# imu_node.net
KiCad netlist of a schematic drawn in EAGLE
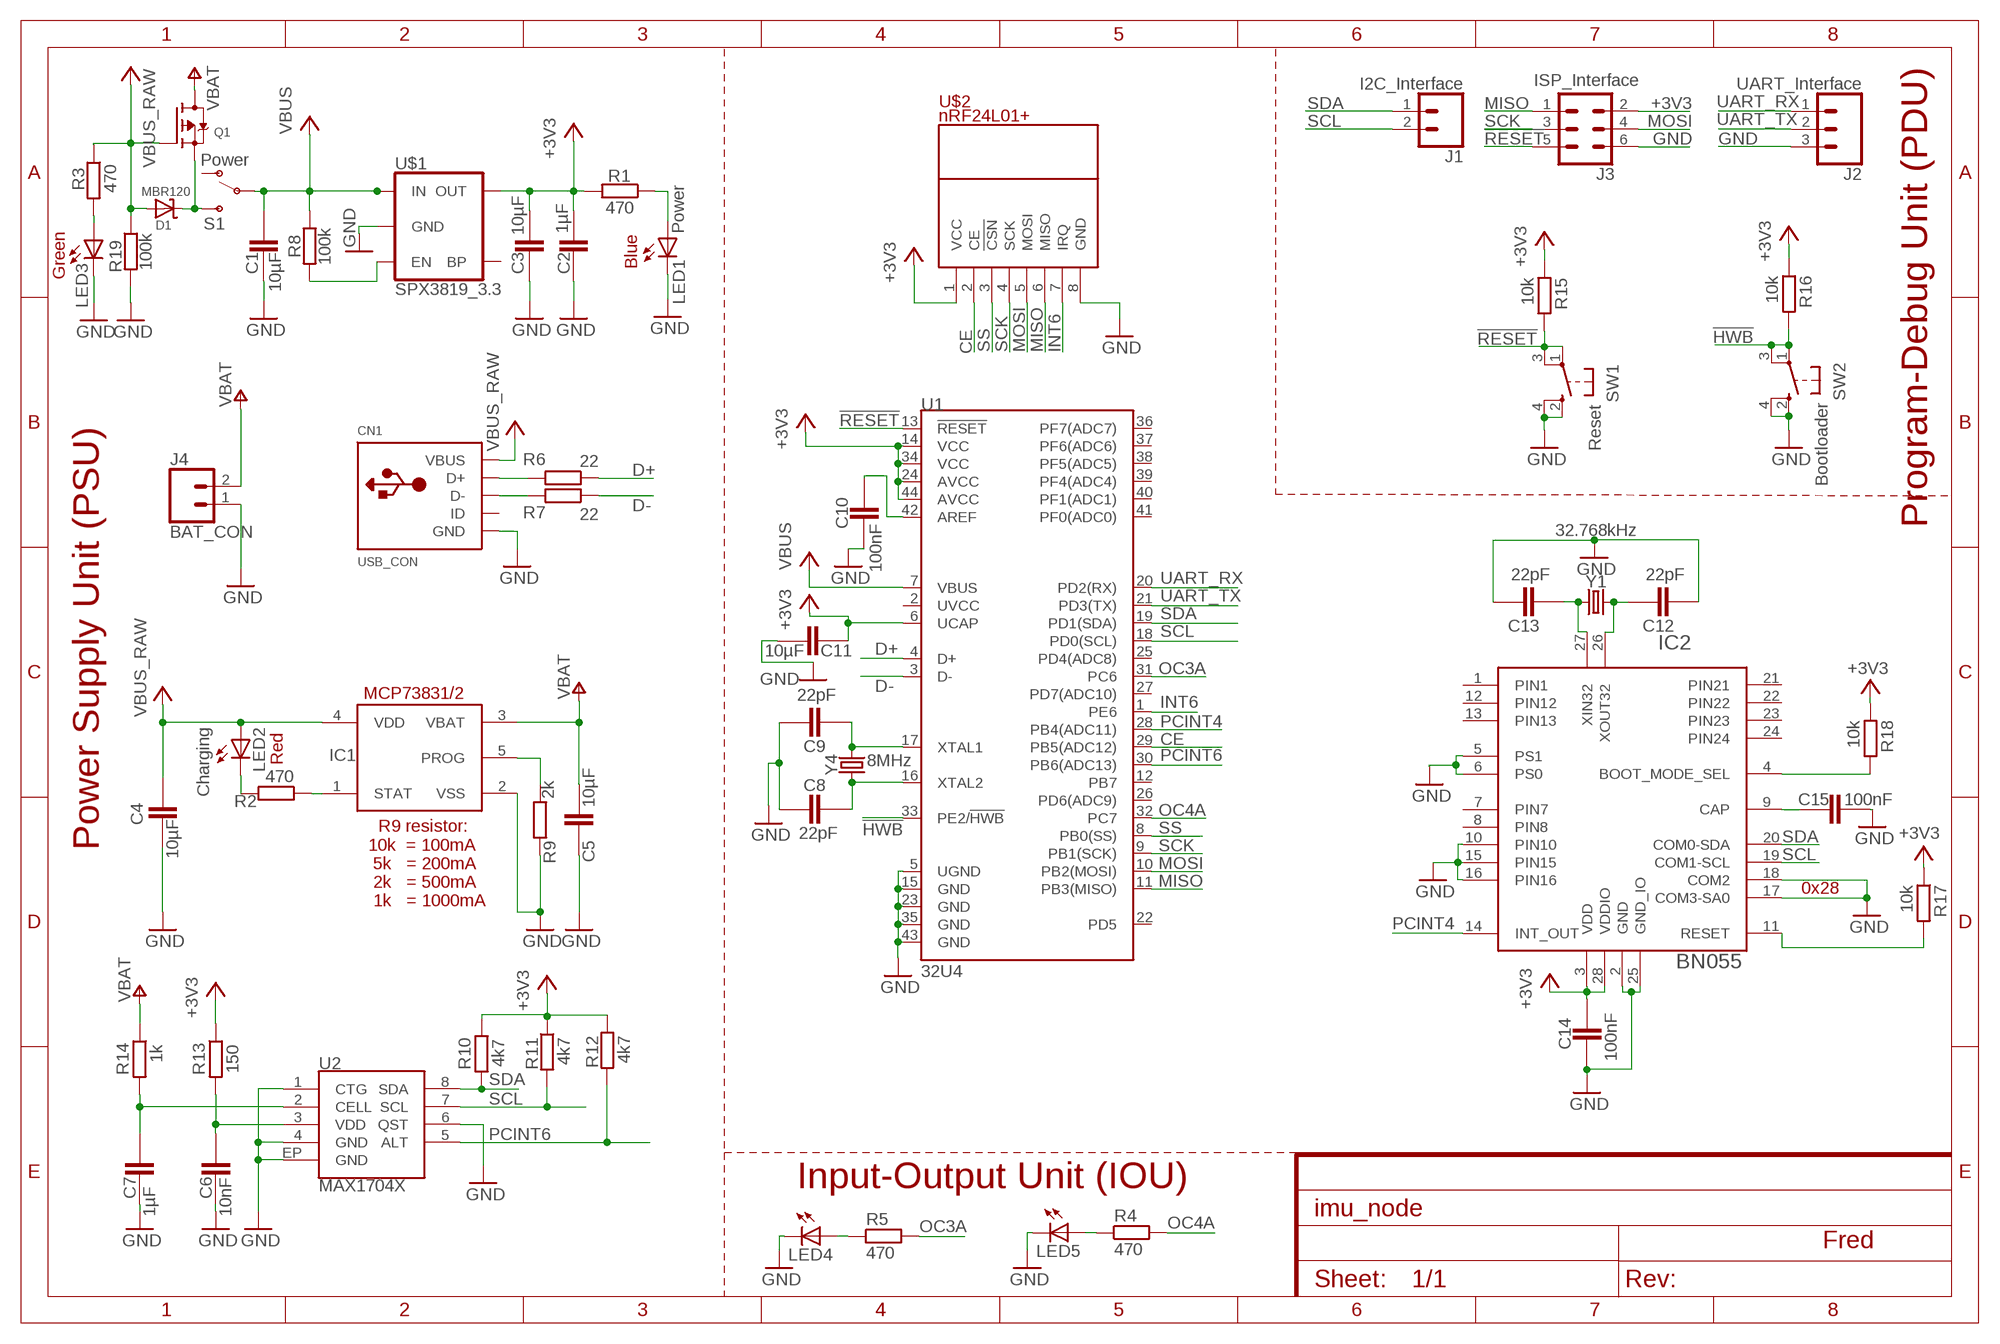
[diagram p0: schematic, sheet 1]

(export (version "E")
  (design (tool "Eeschema 10.0.6"))
  (components
    (comp (ref "C1")
      (value "10µF")
      (footprint "eagle-import:CAPC1608X92N")
      (libsource (lib "eagle-import") (part "CAPACITOR_0603"))
    )
    (comp (ref "C2")
      (value "1µF")
      (footprint "eagle-import:CAPC1608X92N")
      (libsource (lib "eagle-import") (part "CAPACITOR_0603"))
    )
    (comp (ref "C3")
      (value "10µF")
      (footprint "eagle-import:CAPC1608X92N")
      (libsource (lib "eagle-import") (part "CAPACITOR_0603"))
    )
    (comp (ref "C4")
      (value "10µF")
      (footprint "eagle-import:CAPC1608X92N")
      (libsource (lib "eagle-import") (part "CAPACITOR_0603"))
    )
    (comp (ref "C5")
      (value "10µF")
      (footprint "eagle-import:CAPC1608X92N")
      (libsource (lib "eagle-import") (part "CAPACITOR_0603"))
    )
    (comp (ref "C6")
      (value "10nF")
      (footprint "eagle-import:CAPC1608X92N")
      (libsource (lib "eagle-import") (part "CAPACITOR_0603"))
    )
    (comp (ref "C7")
      (value "1µF")
      (footprint "eagle-import:CAPC1608X92N")
      (libsource (lib "eagle-import") (part "CAPACITOR_0603"))
    )
    (comp (ref "C8")
      (value "22pF")
      (footprint "eagle-import:CAPC1608X92N")
      (libsource (lib "eagle-import") (part "CAPACITOR_0603"))
    )
    (comp (ref "C9")
      (value "22pF")
      (footprint "eagle-import:CAPC1608X92N")
      (libsource (lib "eagle-import") (part "CAPACITOR_0603"))
    )
    (comp (ref "C10")
      (value "100nF")
      (footprint "eagle-import:CAPC1608X92N")
      (libsource (lib "eagle-import") (part "CAPACITOR_0603"))
    )
    (comp (ref "C11")
      (value "10µF")
      (footprint "eagle-import:CAPC1608X92N")
      (libsource (lib "eagle-import") (part "CAPACITOR_0603"))
    )
    (comp (ref "C12")
      (value "22pF")
      (footprint "eagle-import:CAPC1608X92N")
      (libsource (lib "eagle-import") (part "CAPACITOR_0603"))
    )
    (comp (ref "C13")
      (value "22pF")
      (footprint "eagle-import:CAPC1608X92N")
      (libsource (lib "eagle-import") (part "CAPACITOR_0603"))
    )
    (comp (ref "C14")
      (value "100nF")
      (footprint "eagle-import:CAPC1608X92N")
      (libsource (lib "eagle-import") (part "CAPACITOR_0603"))
    )
    (comp (ref "C15")
      (value "100nF")
      (footprint "eagle-import:CAPC1608X92N")
      (libsource (lib "eagle-import") (part "CAPACITOR_0603"))
    )
    (comp (ref "CN1")
      (value "USB_CON")
      (footprint "eagle-import:USB-MINIB")
      (libsource (lib "eagle-import") (part "USBMINIB"))
    )
    (comp (ref "D1")
      (value "MBR120")
      (footprint "eagle-import:SOD-123FL")
      (libsource (lib "eagle-import") (part "DIODE_SOD-123FL"))
    )
    (comp (ref "IC1")
      (value "MCP73831/OT")
      (footprint "eagle-import:SOT23-5L")
      (libsource (lib "eagle-import") (part "MCP73831/OT"))
    )
    (comp (ref "IC2")
      (value "BN055")
      (footprint "eagle-import:LGA-28_3.80X5.20_0.5")
      (fields (field (name "PART_NUMBER") "BNO055"))
      (libsource (lib "eagle-import") (part "1658_BNO055"))
    )
    (comp (ref "J1")
      (value "I2C_Interface")
      (footprint "eagle-import:1X02")
      (libsource (lib "eagle-import") (part "CONN_02"))
    )
    (comp (ref "J2")
      (value "UART_Interface")
      (footprint "eagle-import:1X03")
      (libsource (lib "eagle-import") (part "CONN_03"))
    )
    (comp (ref "J3")
      (value "ISP_Interface")
      (footprint "eagle-import:2X3")
      (libsource (lib "eagle-import") (part "CONN_03X2FEMALE"))
    )
    (comp (ref "J4")
      (value "BAT_CON")
      (footprint "eagle-import:1X02")
      (libsource (lib "eagle-import") (part "CONN_02"))
    )
    (comp (ref "LED1")
      (value "Power")
      (footprint "eagle-import:CHIPLED_0603")
      (libsource (lib "eagle-import") (part "LEDCHIPLED_0603"))
    )
    (comp (ref "LED2")
      (value "Charging")
      (footprint "eagle-import:CHIPLED_0603")
      (libsource (lib "eagle-import") (part "LEDCHIPLED_0603"))
    )
    (comp (ref "LED3")
      (value "USB")
      (footprint "eagle-import:CHIPLED_0603")
      (libsource (lib "eagle-import") (part "LEDCHIPLED_0603"))
    )
    (comp (ref "LED4")
      (value "LEDCHIPLED_0603")
      (footprint "eagle-import:CHIPLED_0603")
      (libsource (lib "eagle-import") (part "LEDCHIPLED_0603"))
    )
    (comp (ref "LED5")
      (value "LEDCHIPLED_0603")
      (footprint "eagle-import:CHIPLED_0603")
      (libsource (lib "eagle-import") (part "LEDCHIPLED_0603"))
    )
    (comp (ref "Q1")
      (value "MICROBUILDER_MOSFET-P")
      (footprint "eagle-import:MICROBUILDER_SOT23-R")
      (libsource (lib "eagle-import") (part "MICROBUILDER_MOSFET-P"))
    )
    (comp (ref "R1")
      (value "470")
      (footprint "eagle-import:RESC1608X55N")
      (libsource (lib "eagle-import") (part "RESISTOR_0603"))
    )
    (comp (ref "R2")
      (value "470")
      (footprint "eagle-import:RESC1608X55N")
      (libsource (lib "eagle-import") (part "RESISTOR_0603"))
    )
    (comp (ref "R3")
      (value "470")
      (footprint "eagle-import:RESC1608X55N")
      (libsource (lib "eagle-import") (part "RESISTOR_0603"))
    )
    (comp (ref "R4")
      (value "470")
      (footprint "eagle-import:RESC1608X55N")
      (libsource (lib "eagle-import") (part "RESISTOR_0603"))
    )
    (comp (ref "R5")
      (value "470")
      (footprint "eagle-import:RESC1608X55N")
      (libsource (lib "eagle-import") (part "RESISTOR_0603"))
    )
    (comp (ref "R6")
      (value "22")
      (footprint "eagle-import:RESC1608X55N")
      (libsource (lib "eagle-import") (part "RESISTOR_0603"))
    )
    (comp (ref "R7")
      (value "22")
      (footprint "eagle-import:RESC1608X55N")
      (libsource (lib "eagle-import") (part "RESISTOR_0603"))
    )
    (comp (ref "R8")
      (value "100k")
      (footprint "eagle-import:RESC1608X55N")
      (libsource (lib "eagle-import") (part "RESISTOR_0603"))
    )
    (comp (ref "R9")
      (value "2k")
      (footprint "eagle-import:RESC1608X55N")
      (libsource (lib "eagle-import") (part "RESISTOR_0603"))
    )
    (comp (ref "R10")
      (value "4k7")
      (footprint "eagle-import:RESC1608X55N")
      (libsource (lib "eagle-import") (part "RESISTOR_0603"))
    )
    (comp (ref "R11")
      (value "4k7")
      (footprint "eagle-import:RESC1608X55N")
      (libsource (lib "eagle-import") (part "RESISTOR_0603"))
    )
    (comp (ref "R12")
      (value "4k7")
      (footprint "eagle-import:RESC1608X55N")
      (libsource (lib "eagle-import") (part "RESISTOR_0603"))
    )
    (comp (ref "R13")
      (value "150")
      (footprint "eagle-import:RESC1608X55N")
      (libsource (lib "eagle-import") (part "RESISTOR_0603"))
    )
    (comp (ref "R14")
      (value "1k")
      (footprint "eagle-import:RESC1608X55N")
      (libsource (lib "eagle-import") (part "RESISTOR_0603"))
    )
    (comp (ref "R15")
      (value "10k")
      (footprint "eagle-import:RESC1608X55N")
      (libsource (lib "eagle-import") (part "RESISTOR_0603"))
    )
    (comp (ref "R16")
      (value "10k")
      (footprint "eagle-import:RESC1608X55N")
      (libsource (lib "eagle-import") (part "RESISTOR_0603"))
    )
    (comp (ref "R17")
      (value "10k")
      (footprint "eagle-import:RESC1608X55N")
      (libsource (lib "eagle-import") (part "RESISTOR_0603"))
    )
    (comp (ref "R18")
      (value "10k")
      (footprint "eagle-import:RESC1608X55N")
      (libsource (lib "eagle-import") (part "RESISTOR_0603"))
    )
    (comp (ref "R19")
      (value "100k")
      (footprint "eagle-import:RESC1608X55N")
      (libsource (lib "eagle-import") (part "RESISTOR_0603"))
    )
    (comp (ref "S1")
      (value "Power")
      (footprint "eagle-import:SWITCH_SPST_SMD_A")
      (libsource (lib "eagle-import") (part "SWITCH-SPDT-SMD-RIGHT-ANGLE"))
    )
    (comp (ref "SW1")
      (value "Reset")
      (footprint "eagle-import:KMR2")
      (libsource (lib "eagle-import") (part "SPST_TACT-KMR2"))
    )
    (comp (ref "SW2")
      (value "Bootloader")
      (footprint "eagle-import:KMR2")
      (libsource (lib "eagle-import") (part "SPST_TACT-KMR2"))
    )
    (comp (ref "U$1")
      (value "SPX3819_3.3")
      (footprint "eagle-import:SOT23-5")
      (libsource (lib "eagle-import") (part "V_REG_SPX3819-SOT23-5"))
    )
    (comp (ref "U$2")
      (value "nRF24L01+")
      (footprint "eagle-import:6-PIN-BREAKOUT")
      (libsource (lib "eagle-import") (part "6-PIN-BREAKOUT6-PIN-BREAKOUT"))
    )
    (comp (ref "U1")
      (value "32U4")
      (footprint "eagle-import:TQFP44")
      (libsource (lib "eagle-import") (part "ATMEGA32U4TQFP-44"))
    )
    (comp (ref "U2")
      (value "MAX1704X")
      (footprint "eagle-import:TDFN-8")
      (libsource (lib "eagle-import") (part "MAX1704X"))
    )
    (comp (ref "Y1")
      (value "32.768kHz")
      (footprint "eagle-import:CRYSTAL-SMD-3.2X1.5MM")
      (libsource (lib "eagle-import") (part "CRYSTAL-32.768KHZSMD-3.2X1.5"))
    )
    (comp (ref "Y4")
      (value "8MHz")
      (footprint "eagle-import:CRYSTAL-SMD-5X3.2-4PAD")
      (libsource (lib "eagle-import") (part "CRYSTAL-8MHZSMD-5X3.2"))
    )
  )
  (nets
    (net (code "1") (name "+3V3") (class "Default")
      (node (ref "C11") (pin "1") (pinfunction "1_1") (pintype "passive"))
      (node (ref "C14") (pin "1") (pinfunction "1_1") (pintype "passive"))
      (node (ref "C2") (pin "2") (pinfunction "2_2") (pintype "passive"))
      (node (ref "C3") (pin "2") (pinfunction "2_2") (pintype "passive"))
      (node (ref "IC2") (pin "28") (pinfunction "VDDIO_28") (pintype "power_in"))
      (node (ref "IC2") (pin "3") (pinfunction "VDD_3") (pintype "power_in"))
      (node (ref "J3") (pin "2") (pinfunction "2_2") (pintype "bidirectional"))
      (node (ref "R1") (pin "2") (pinfunction "2_2") (pintype "passive"))
      (node (ref "R10") (pin "1") (pinfunction "1_1") (pintype "passive"))
      (node (ref "R11") (pin "1") (pinfunction "1_1") (pintype "passive"))
      (node (ref "R12") (pin "1") (pinfunction "1_1") (pintype "passive"))
      (node (ref "R13") (pin "1") (pinfunction "1_1") (pintype "passive"))
      (node (ref "R15") (pin "1") (pinfunction "1_1") (pintype "passive"))
      (node (ref "R16") (pin "1") (pinfunction "1_1") (pintype "passive"))
      (node (ref "R17") (pin "1") (pinfunction "1_1") (pintype "passive"))
      (node (ref "R18") (pin "1") (pinfunction "1_1") (pintype "passive"))
      (node (ref "U$1") (pin "5") (pinfunction "OUT_5") (pintype "passive"))
      (node (ref "U$2") (pin "1") (pinfunction "VCC_1") (pintype "bidirectional"))
      (node (ref "U1") (pin "14") (pinfunction "VCC_14") (pintype "bidirectional"))
      (node (ref "U1") (pin "24") (pinfunction "AVCC_24") (pintype "bidirectional"))
      (node (ref "U1") (pin "34") (pinfunction "VCC_34") (pintype "bidirectional"))
      (node (ref "U1") (pin "44") (pinfunction "AVCC_44") (pintype "bidirectional"))
      (node (ref "U1") (pin "6") (pinfunction "UCAP_6") (pintype "bidirectional"))
    )
    (net (code "2") (name "/CE") (class "Default")
      (node (ref "U$2") (pin "2") (pinfunction "CE_2") (pintype "bidirectional"))
      (node (ref "U1") (pin "29") (pinfunction "PB5(ADC12)_29") (pintype "bidirectional"))
    )
    (net (code "3") (name "/D+") (class "Default")
      (node (ref "R6") (pin "1") (pinfunction "1_1") (pintype "passive"))
      (node (ref "U1") (pin "4") (pinfunction "D+_4") (pintype "bidirectional"))
    )
    (net (code "4") (name "/D-") (class "Default")
      (node (ref "R7") (pin "1") (pinfunction "1_1") (pintype "passive"))
      (node (ref "U1") (pin "3") (pinfunction "D-_3") (pintype "bidirectional"))
    )
    (net (code "5") (name "/INT6") (class "Default")
      (node (ref "U$2") (pin "7") (pinfunction "IRQ_7") (pintype "bidirectional"))
      (node (ref "U1") (pin "1") (pinfunction "PE6_1") (pintype "bidirectional"))
    )
    (net (code "6") (name "/MISO") (class "Default")
      (node (ref "J3") (pin "1") (pinfunction "1_1") (pintype "bidirectional"))
      (node (ref "U$2") (pin "6") (pinfunction "MISO_6") (pintype "bidirectional"))
      (node (ref "U1") (pin "11") (pinfunction "PB3(MISO)_11") (pintype "bidirectional"))
    )
    (net (code "7") (name "/MOSI") (class "Default")
      (node (ref "J3") (pin "4") (pinfunction "4_4") (pintype "bidirectional"))
      (node (ref "U$2") (pin "5") (pinfunction "MOSI_5") (pintype "bidirectional"))
      (node (ref "U1") (pin "10") (pinfunction "PB2(MOSI)_10") (pintype "bidirectional"))
    )
    (net (code "8") (name "/OC3A") (class "Default")
      (node (ref "R5") (pin "2") (pinfunction "2_2") (pintype "passive"))
      (node (ref "U1") (pin "31") (pinfunction "PC6_31") (pintype "bidirectional"))
    )
    (net (code "9") (name "/OC4A") (class "Default")
      (node (ref "R4") (pin "2") (pinfunction "2_2") (pintype "passive"))
      (node (ref "U1") (pin "32") (pinfunction "PC7_32") (pintype "bidirectional"))
    )
    (net (code "10") (name "/PCINT4") (class "Default")
      (node (ref "IC2") (pin "14") (pinfunction "INT_OUT_14") (pintype "output"))
      (node (ref "U1") (pin "28") (pinfunction "PB4(ADC11)_28") (pintype "bidirectional"))
    )
    (net (code "11") (name "/PCINT6") (class "Default")
      (node (ref "R12") (pin "2") (pinfunction "2_2") (pintype "passive"))
      (node (ref "U1") (pin "30") (pinfunction "PB6(ADC13)_30") (pintype "bidirectional"))
      (node (ref "U2") (pin "5") (pinfunction "ALT_5") (pintype "bidirectional"))
    )
    (net (code "12") (name "/SCK") (class "Default")
      (node (ref "J3") (pin "3") (pinfunction "3_3") (pintype "bidirectional"))
      (node (ref "U$2") (pin "4") (pinfunction "SCK_4") (pintype "bidirectional"))
      (node (ref "U1") (pin "9") (pinfunction "PB1(SCK)_9") (pintype "bidirectional"))
    )
    (net (code "13") (name "/SCL") (class "Default")
      (node (ref "IC2") (pin "19") (pinfunction "COM1-SCL_19") (pintype "bidirectional"))
      (node (ref "J1") (pin "2") (pinfunction "2_2") (pintype "passive"))
      (node (ref "R11") (pin "2") (pinfunction "2_2") (pintype "passive"))
      (node (ref "U1") (pin "18") (pinfunction "PD0(SCL)_18") (pintype "bidirectional"))
      (node (ref "U2") (pin "7") (pinfunction "SCL_7") (pintype "bidirectional"))
    )
    (net (code "14") (name "/SDA") (class "Default")
      (node (ref "IC2") (pin "20") (pinfunction "COM0-SDA_20") (pintype "bidirectional"))
      (node (ref "J1") (pin "1") (pinfunction "1_1") (pintype "passive"))
      (node (ref "R10") (pin "2") (pinfunction "2_2") (pintype "passive"))
      (node (ref "U1") (pin "19") (pinfunction "PD1(SDA)_19") (pintype "bidirectional"))
      (node (ref "U2") (pin "8") (pinfunction "SDA_8") (pintype "bidirectional"))
    )
    (net (code "15") (name "/SS") (class "Default")
      (node (ref "U$2") (pin "3") (pinfunction "~{CSN}_3") (pintype "bidirectional"))
      (node (ref "U1") (pin "8") (pinfunction "PB0(SS)_8") (pintype "bidirectional"))
    )
    (net (code "16") (name "/UART_RX") (class "Default")
      (node (ref "J2") (pin "1") (pinfunction "1_1") (pintype "passive"))
      (node (ref "U1") (pin "20") (pinfunction "PD2(RX)_20") (pintype "bidirectional"))
    )
    (net (code "17") (name "/UART_TX") (class "Default")
      (node (ref "J2") (pin "2") (pinfunction "2_2") (pintype "passive"))
      (node (ref "U1") (pin "21") (pinfunction "PD3(TX)_21") (pintype "bidirectional"))
    )
    (net (code "18") (name "/~{HWB}") (class "Default")
      (node (ref "R16") (pin "2") (pinfunction "2_2") (pintype "passive"))
      (node (ref "SW2") (pin "1") (pinfunction "P_1") (pintype "passive"))
      (node (ref "SW2") (pin "3") (pinfunction "P1_3") (pintype "passive"))
      (node (ref "U1") (pin "33") (pinfunction "PE2/~{HWB}_33") (pintype "bidirectional"))
    )
    (net (code "19") (name "/~{RESET}") (class "Default")
      (node (ref "J3") (pin "5") (pinfunction "5_5") (pintype "bidirectional"))
      (node (ref "R15") (pin "2") (pinfunction "2_2") (pintype "passive"))
      (node (ref "SW1") (pin "1") (pinfunction "P_1") (pintype "passive"))
      (node (ref "SW1") (pin "3") (pinfunction "P1_3") (pintype "passive"))
      (node (ref "U1") (pin "13") (pinfunction "~{RESET}_13") (pintype "bidirectional"))
    )
    (net (code "20") (name "GND") (class "Default")
      (node (ref "C1") (pin "1") (pinfunction "1_1") (pintype "passive"))
      (node (ref "C10") (pin "2") (pinfunction "2_2") (pintype "passive"))
      (node (ref "C11") (pin "2") (pinfunction "2_2") (pintype "passive"))
      (node (ref "C12") (pin "1") (pinfunction "1_1") (pintype "passive"))
      (node (ref "C13") (pin "2") (pinfunction "2_2") (pintype "passive"))
      (node (ref "C14") (pin "2") (pinfunction "2_2") (pintype "passive"))
      (node (ref "C15") (pin "2") (pinfunction "2_2") (pintype "passive"))
      (node (ref "C2") (pin "1") (pinfunction "1_1") (pintype "passive"))
      (node (ref "C3") (pin "1") (pinfunction "1_1") (pintype "passive"))
      (node (ref "C4") (pin "1") (pinfunction "1_1") (pintype "passive"))
      (node (ref "C5") (pin "1") (pinfunction "1_1") (pintype "passive"))
      (node (ref "C6") (pin "1") (pinfunction "1_1") (pintype "passive"))
      (node (ref "C7") (pin "1") (pinfunction "1_1") (pintype "passive"))
      (node (ref "C8") (pin "2") (pinfunction "2_2") (pintype "passive"))
      (node (ref "C9") (pin "2") (pinfunction "2_2") (pintype "passive"))
      (node (ref "CN1") (pin "GND") (pinfunction "GND_GND") (pintype "power_in"))
      (node (ref "IC1") (pin "2") (pinfunction "VSS_2") (pintype "power_in"))
      (node (ref "IC2") (pin "10") (pinfunction "PIN10_10") (pintype "passive"))
      (node (ref "IC2") (pin "15") (pinfunction "PIN15_15") (pintype "passive"))
      (node (ref "IC2") (pin "16") (pinfunction "PIN16_16") (pintype "passive"))
      (node (ref "IC2") (pin "17") (pinfunction "COM3-SA0_17") (pintype "bidirectional"))
      (node (ref "IC2") (pin "18") (pinfunction "COM2_18") (pintype "bidirectional"))
      (node (ref "IC2") (pin "2") (pinfunction "GND_2") (pintype "power_in"))
      (node (ref "IC2") (pin "25") (pinfunction "GND_IO_25") (pintype "power_in"))
      (node (ref "IC2") (pin "5") (pinfunction "PS1_5") (pintype "input"))
      (node (ref "IC2") (pin "6") (pinfunction "PS0_6") (pintype "input"))
      (node (ref "J2") (pin "3") (pinfunction "3_3") (pintype "passive"))
      (node (ref "J3") (pin "6") (pinfunction "6_6") (pintype "bidirectional"))
      (node (ref "J4") (pin "1") (pinfunction "1_1") (pintype "passive"))
      (node (ref "LED1") (pin "C") (pinfunction "C_C") (pintype "passive"))
      (node (ref "LED3") (pin "C") (pinfunction "C_C") (pintype "passive"))
      (node (ref "LED4") (pin "C") (pinfunction "C_C") (pintype "passive"))
      (node (ref "LED5") (pin "C") (pinfunction "C_C") (pintype "passive"))
      (node (ref "R19") (pin "2") (pinfunction "2_2") (pintype "passive"))
      (node (ref "R9") (pin "2") (pinfunction "2_2") (pintype "passive"))
      (node (ref "SW1") (pin "2") (pinfunction "S_2") (pintype "passive"))
      (node (ref "SW1") (pin "4") (pinfunction "S1_4") (pintype "passive"))
      (node (ref "SW2") (pin "2") (pinfunction "S_2") (pintype "passive"))
      (node (ref "SW2") (pin "4") (pinfunction "S1_4") (pintype "passive"))
      (node (ref "U$1") (pin "2") (pinfunction "GND_2") (pintype "input"))
      (node (ref "U$2") (pin "8") (pinfunction "GND_8") (pintype "bidirectional"))
      (node (ref "U1") (pin "15") (pinfunction "GND_15") (pintype "bidirectional"))
      (node (ref "U1") (pin "23") (pinfunction "GND_23") (pintype "bidirectional"))
      (node (ref "U1") (pin "35") (pinfunction "GND_35") (pintype "bidirectional"))
      (node (ref "U1") (pin "43") (pinfunction "GND_43") (pintype "bidirectional"))
      (node (ref "U1") (pin "5") (pinfunction "UGND_5") (pintype "bidirectional"))
      (node (ref "U2") (pin "1") (pinfunction "CTG_1") (pintype "bidirectional"))
      (node (ref "U2") (pin "4") (pinfunction "GND_4") (pintype "bidirectional"))
      (node (ref "U2") (pin "6") (pinfunction "QST_6") (pintype "bidirectional"))
      (node (ref "U2") (pin "EP") (pinfunction "GND_EP") (pintype "bidirectional"))
    )
    (net (code "21") (name "Net-(CN1-PadD+)") (class "Default")
      (node (ref "CN1") (pin "D+") (pinfunction "D+_D+") (pintype "bidirectional"))
      (node (ref "R6") (pin "2") (pinfunction "2_2") (pintype "passive"))
    )
    (net (code "22") (name "Net-(CN1-PadD-)") (class "Default")
      (node (ref "CN1") (pin "D-") (pinfunction "D-_D-") (pintype "bidirectional"))
      (node (ref "R7") (pin "2") (pinfunction "2_2") (pintype "passive"))
    )
    (net (code "23") (name "Net-(IC1-PROG)") (class "Default")
      (node (ref "IC1") (pin "5") (pinfunction "PROG_5") (pintype "input"))
      (node (ref "R9") (pin "1") (pinfunction "1_1") (pintype "passive"))
    )
    (net (code "24") (name "Net-(IC1-STAT)") (class "Default")
      (node (ref "IC1") (pin "1") (pinfunction "STAT_1") (pintype "output"))
      (node (ref "R2") (pin "1") (pinfunction "1_1") (pintype "passive"))
    )
    (net (code "25") (name "Net-(IC2-BOOT_MODE_SEL)") (class "Default")
      (node (ref "IC2") (pin "4") (pinfunction "BOOT_MODE_SEL_4") (pintype "input"))
      (node (ref "R18") (pin "2") (pinfunction "2_2") (pintype "passive"))
    )
    (net (code "26") (name "Net-(IC2-CAP)") (class "Default")
      (node (ref "C15") (pin "1") (pinfunction "1_1") (pintype "passive"))
      (node (ref "IC2") (pin "9") (pinfunction "CAP_9") (pintype "tri_state"))
    )
    (net (code "27") (name "Net-(IC2-RESET)") (class "Default")
      (node (ref "IC2") (pin "11") (pinfunction "RESET_11") (pintype "input"))
      (node (ref "R17") (pin "2") (pinfunction "2_2") (pintype "passive"))
    )
    (net (code "28") (name "Net-(IC2-XIN32)") (class "Default")
      (node (ref "C13") (pin "1") (pinfunction "1_1") (pintype "passive"))
      (node (ref "IC2") (pin "27") (pinfunction "XIN32_27") (pintype "bidirectional"))
      (node (ref "Y1") (pin "P$1") (pinfunction "1_P$1") (pintype "passive"))
    )
    (net (code "29") (name "Net-(IC2-XOUT32)") (class "Default")
      (node (ref "C12") (pin "2") (pinfunction "2_2") (pintype "passive"))
      (node (ref "IC2") (pin "26") (pinfunction "XOUT32_26") (pintype "output"))
      (node (ref "Y1") (pin "P$2") (pinfunction "2_P$2") (pintype "passive"))
    )
    (net (code "30") (name "Net-(LED1-PadA)") (class "Default")
      (node (ref "LED1") (pin "A") (pinfunction "A_A") (pintype "passive"))
      (node (ref "R1") (pin "1") (pinfunction "1_1") (pintype "passive"))
    )
    (net (code "31") (name "Net-(LED2-PadC)") (class "Default")
      (node (ref "LED2") (pin "C") (pinfunction "C_C") (pintype "passive"))
      (node (ref "R2") (pin "2") (pinfunction "2_2") (pintype "passive"))
    )
    (net (code "32") (name "Net-(LED3-PadA)") (class "Default")
      (node (ref "LED3") (pin "A") (pinfunction "A_A") (pintype "passive"))
      (node (ref "R3") (pin "2") (pinfunction "2_2") (pintype "passive"))
    )
    (net (code "33") (name "Net-(LED4-PadA)") (class "Default")
      (node (ref "LED4") (pin "A") (pinfunction "A_A") (pintype "passive"))
      (node (ref "R5") (pin "1") (pinfunction "1_1") (pintype "passive"))
    )
    (net (code "34") (name "Net-(LED5-PadA)") (class "Default")
      (node (ref "LED5") (pin "A") (pinfunction "A_A") (pintype "passive"))
      (node (ref "R4") (pin "1") (pinfunction "1_1") (pintype "passive"))
    )
    (net (code "35") (name "Net-(Q1-S)") (class "Default")
      (node (ref "D1") (pin "C") (pinfunction "C_C") (pintype "passive"))
      (node (ref "Q1") (pin "2") (pinfunction "S_2") (pintype "passive"))
      (node (ref "S1") (pin "3") (pinfunction "S_3") (pintype "passive"))
    )
    (net (code "36") (name "Net-(U$1-EN)") (class "Default")
      (node (ref "R8") (pin "2") (pinfunction "2_2") (pintype "passive"))
      (node (ref "U$1") (pin "3") (pinfunction "EN_3") (pintype "input"))
    )
    (net (code "37") (name "Net-(U1-AREF)") (class "Default")
      (node (ref "C10") (pin "1") (pinfunction "1_1") (pintype "passive"))
      (node (ref "U1") (pin "42") (pinfunction "AREF_42") (pintype "bidirectional"))
    )
    (net (code "38") (name "Net-(U1-XTAL1)") (class "Default")
      (node (ref "C9") (pin "1") (pinfunction "1_1") (pintype "passive"))
      (node (ref "U1") (pin "17") (pinfunction "XTAL1_17") (pintype "bidirectional"))
      (node (ref "Y4") (pin "3") (pinfunction "2_3") (pintype "passive"))
    )
    (net (code "39") (name "Net-(U1-XTAL2)") (class "Default")
      (node (ref "C8") (pin "1") (pinfunction "1_1") (pintype "passive"))
      (node (ref "U1") (pin "16") (pinfunction "XTAL2_16") (pintype "bidirectional"))
      (node (ref "Y4") (pin "1") (pinfunction "1_1") (pintype "passive"))
    )
    (net (code "40") (name "Net-(U2-CELL)") (class "Default")
      (node (ref "C7") (pin "2") (pinfunction "2_2") (pintype "passive"))
      (node (ref "R14") (pin "2") (pinfunction "2_2") (pintype "passive"))
      (node (ref "U2") (pin "2") (pinfunction "CELL_2") (pintype "bidirectional"))
    )
    (net (code "41") (name "Net-(U2-VDD)") (class "Default")
      (node (ref "C6") (pin "2") (pinfunction "2_2") (pintype "passive"))
      (node (ref "R13") (pin "2") (pinfunction "2_2") (pintype "passive"))
      (node (ref "U2") (pin "3") (pinfunction "VDD_3") (pintype "bidirectional"))
    )
    (net (code "42") (name "VBAT") (class "Default")
      (node (ref "C5") (pin "2") (pinfunction "2_2") (pintype "passive"))
      (node (ref "IC1") (pin "3") (pinfunction "VBAT_3") (pintype "bidirectional"))
      (node (ref "J4") (pin "2") (pinfunction "2_2") (pintype "passive"))
      (node (ref "Q1") (pin "3") (pinfunction "D_3") (pintype "passive"))
      (node (ref "R14") (pin "1") (pinfunction "1_1") (pintype "passive"))
    )
    (net (code "43") (name "VBUS") (class "Default")
      (node (ref "C1") (pin "2") (pinfunction "2_2") (pintype "passive"))
      (node (ref "R8") (pin "1") (pinfunction "1_1") (pintype "passive"))
      (node (ref "S1") (pin "2") (pinfunction "P_2") (pintype "passive"))
      (node (ref "U$1") (pin "1") (pinfunction "IN_1") (pintype "input"))
      (node (ref "U1") (pin "7") (pinfunction "VBUS_7") (pintype "bidirectional"))
    )
    (net (code "44") (name "VBUS_RAW") (class "Default")
      (node (ref "C4") (pin "2") (pinfunction "2_2") (pintype "passive"))
      (node (ref "CN1") (pin "VBUS") (pinfunction "VBUS_VBUS") (pintype "power_in"))
      (node (ref "D1") (pin "A") (pinfunction "A_A") (pintype "passive"))
      (node (ref "IC1") (pin "4") (pinfunction "VDD_4") (pintype "power_in"))
      (node (ref "LED2") (pin "A") (pinfunction "A_A") (pintype "passive"))
      (node (ref "Q1") (pin "1") (pinfunction "G_1") (pintype "passive"))
      (node (ref "R19") (pin "1") (pinfunction "1_1") (pintype "passive"))
      (node (ref "R3") (pin "1") (pinfunction "1_1") (pintype "passive"))
    )
    (net (code "45") (name "unconnected-(CN1-PadID)") (class "Default")
      (node (ref "CN1") (pin "ID") (pinfunction "ID_ID") (pintype "bidirectional"))
    )
    (net (code "46") (name "unconnected-(IC2-PIN1-Pad1)") (class "Default")
      (node (ref "IC2") (pin "1") (pinfunction "PIN1_1") (pintype "no_connect"))
    )
    (net (code "47") (name "unconnected-(IC2-PIN7-Pad7)") (class "Default")
      (node (ref "IC2") (pin "7") (pinfunction "PIN7_7") (pintype "tri_state"))
    )
    (net (code "48") (name "unconnected-(IC2-PIN8-Pad8)") (class "Default")
      (node (ref "IC2") (pin "8") (pinfunction "PIN8_8") (pintype "tri_state"))
    )
    (net (code "49") (name "unconnected-(IC2-PIN12-Pad12)") (class "Default")
      (node (ref "IC2") (pin "12") (pinfunction "PIN12_12") (pintype "passive"))
    )
    (net (code "50") (name "unconnected-(IC2-PIN13-Pad13)") (class "Default")
      (node (ref "IC2") (pin "13") (pinfunction "PIN13_13") (pintype "passive"))
    )
    (net (code "51") (name "unconnected-(IC2-PIN21-Pad21)") (class "Default")
      (node (ref "IC2") (pin "21") (pinfunction "PIN21_21") (pintype "passive"))
    )
    (net (code "52") (name "unconnected-(IC2-PIN22-Pad22)") (class "Default")
      (node (ref "IC2") (pin "22") (pinfunction "PIN22_22") (pintype "passive"))
    )
    (net (code "53") (name "unconnected-(IC2-PIN23-Pad23)") (class "Default")
      (node (ref "IC2") (pin "23") (pinfunction "PIN23_23") (pintype "passive"))
    )
    (net (code "54") (name "unconnected-(IC2-PIN24-Pad24)") (class "Default")
      (node (ref "IC2") (pin "24") (pinfunction "PIN24_24") (pintype "passive"))
    )
    (net (code "55") (name "unconnected-(S1-O-Pad1)") (class "Default")
      (node (ref "S1") (pin "1") (pinfunction "O_1") (pintype "passive"))
    )
    (net (code "56") (name "unconnected-(U$1-BP-Pad4)") (class "Default")
      (node (ref "U$1") (pin "4") (pinfunction "BP_4") (pintype "input"))
    )
    (net (code "57") (name "unconnected-(U1-PB7-Pad12)") (class "Default")
      (node (ref "U1") (pin "12") (pinfunction "PB7_12") (pintype "bidirectional"))
    )
    (net (code "58") (name "unconnected-(U1-PD4(ADC8)-Pad25)") (class "Default")
      (node (ref "U1") (pin "25") (pinfunction "PD4(ADC8)_25") (pintype "bidirectional"))
    )
    (net (code "59") (name "unconnected-(U1-PD5-Pad22)") (class "Default")
      (node (ref "U1") (pin "22") (pinfunction "PD5_22") (pintype "bidirectional"))
    )
    (net (code "60") (name "unconnected-(U1-PD6(ADC9)-Pad26)") (class "Default")
      (node (ref "U1") (pin "26") (pinfunction "PD6(ADC9)_26") (pintype "bidirectional"))
    )
    (net (code "61") (name "unconnected-(U1-PD7(ADC10)-Pad27)") (class "Default")
      (node (ref "U1") (pin "27") (pinfunction "PD7(ADC10)_27") (pintype "bidirectional"))
    )
    (net (code "62") (name "unconnected-(U1-PF0(ADC0)-Pad41)") (class "Default")
      (node (ref "U1") (pin "41") (pinfunction "PF0(ADC0)_41") (pintype "bidirectional"))
    )
    (net (code "63") (name "unconnected-(U1-PF1(ADC1)-Pad40)") (class "Default")
      (node (ref "U1") (pin "40") (pinfunction "PF1(ADC1)_40") (pintype "bidirectional"))
    )
    (net (code "64") (name "unconnected-(U1-PF4(ADC4)-Pad39)") (class "Default")
      (node (ref "U1") (pin "39") (pinfunction "PF4(ADC4)_39") (pintype "bidirectional"))
    )
    (net (code "65") (name "unconnected-(U1-PF5(ADC5)-Pad38)") (class "Default")
      (node (ref "U1") (pin "38") (pinfunction "PF5(ADC5)_38") (pintype "bidirectional"))
    )
    (net (code "66") (name "unconnected-(U1-PF6(ADC6)-Pad37)") (class "Default")
      (node (ref "U1") (pin "37") (pinfunction "PF6(ADC6)_37") (pintype "bidirectional"))
    )
    (net (code "67") (name "unconnected-(U1-PF7(ADC7)-Pad36)") (class "Default")
      (node (ref "U1") (pin "36") (pinfunction "PF7(ADC7)_36") (pintype "bidirectional"))
    )
    (net (code "68") (name "unconnected-(U1-UVCC-Pad2)") (class "Default")
      (node (ref "U1") (pin "2") (pinfunction "UVCC_2") (pintype "bidirectional"))
    )
  )
)
